# main_board.net
KiCad netlist of a schematic drawn in EAGLE
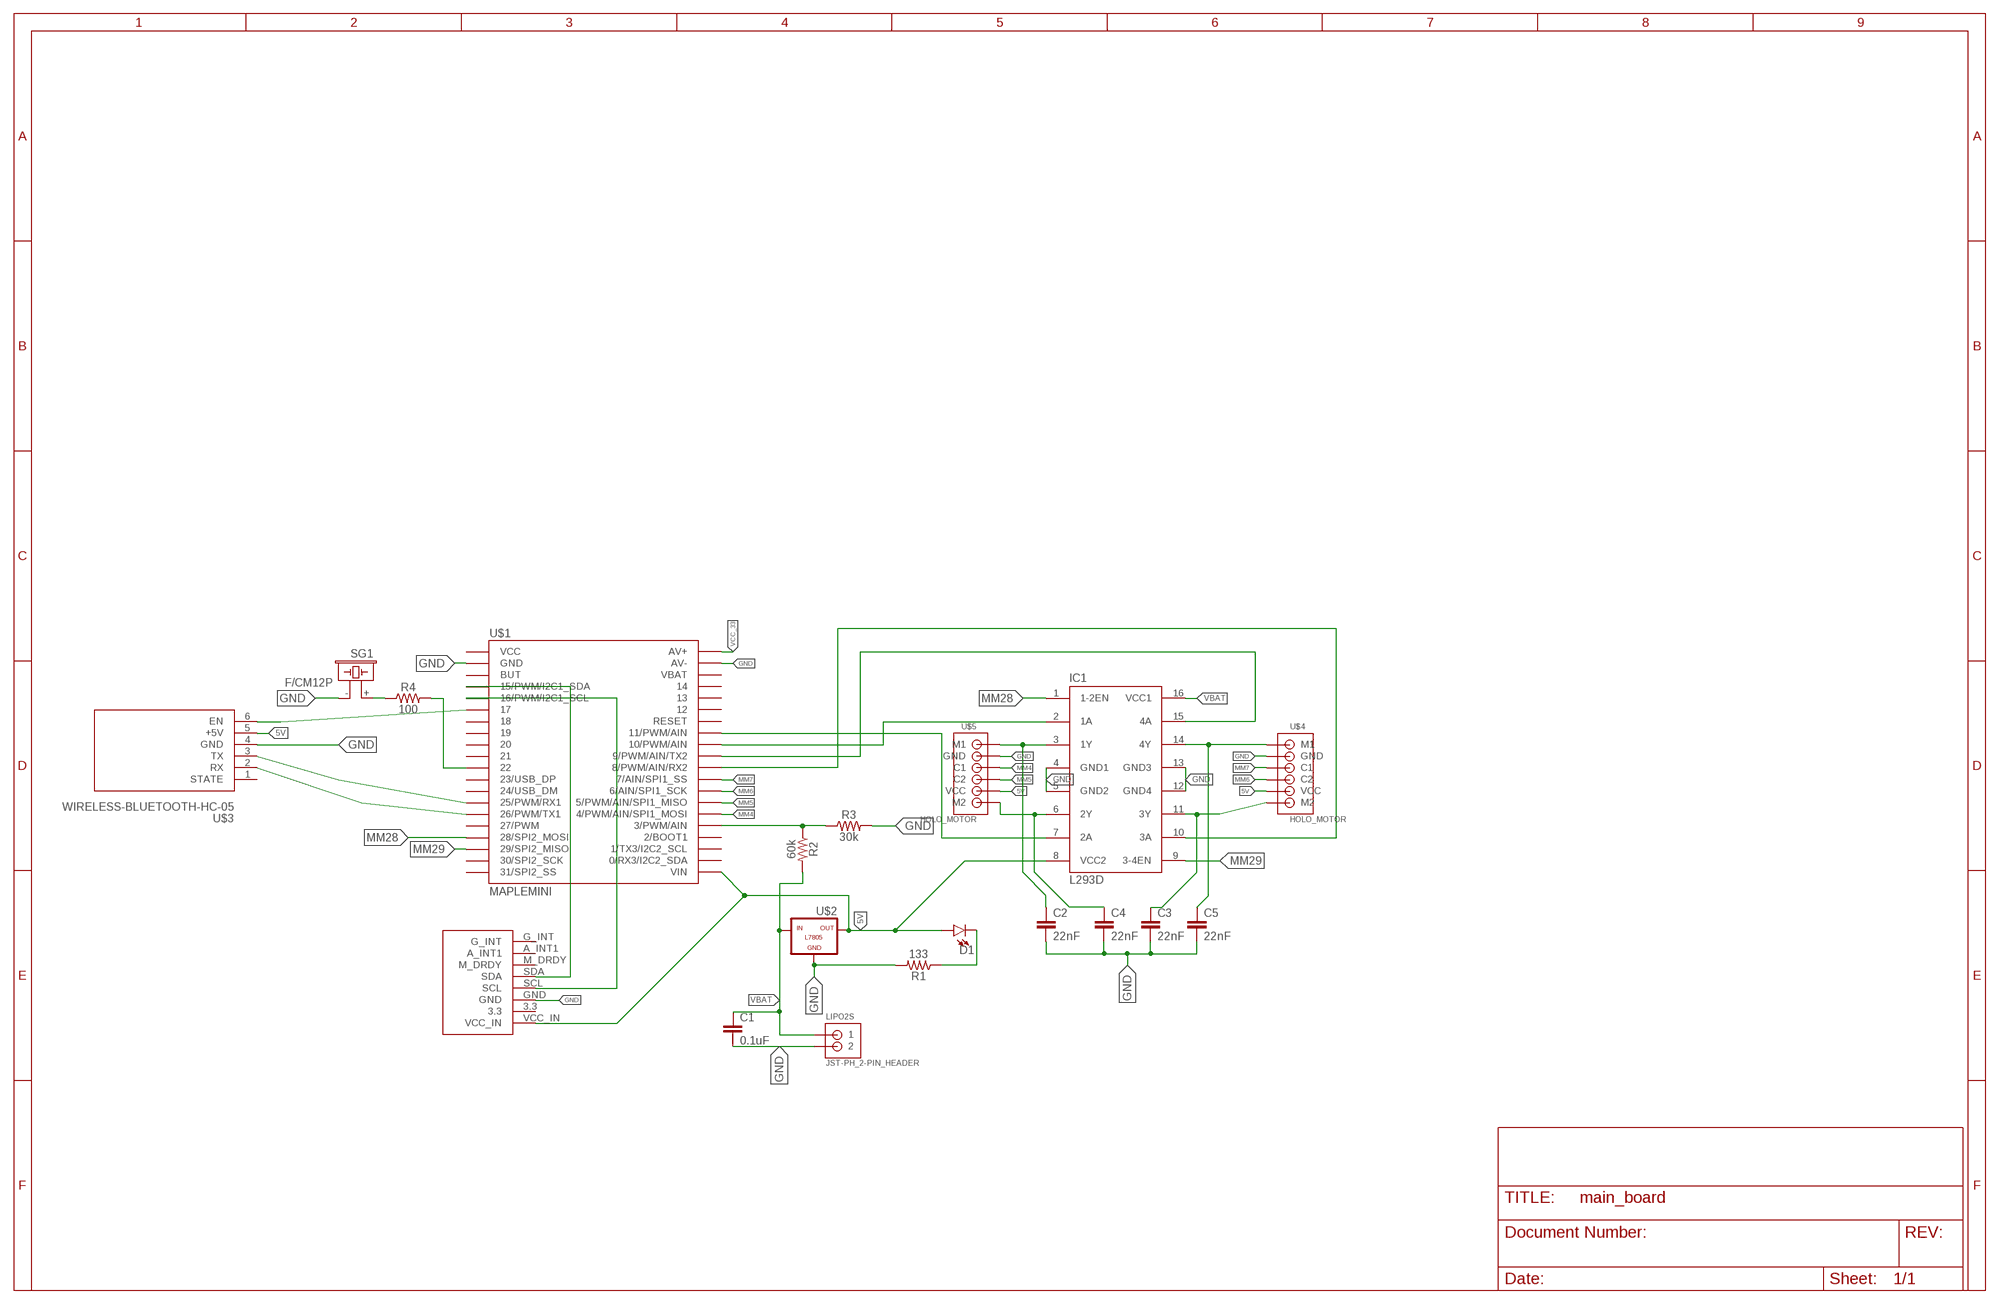
[diagram p0: schematic, sheet 1]

(export (version "E")
  (design (tool "Eeschema 10.0.6"))
  (components
    (comp (ref "C1")
      (value "0.1uF")
      (footprint "eagle-import:0603")
      (libsource (lib "eagle-import") (part "0.1UF-0603-25V-(+80/-20%)"))
    )
    (comp (ref "C2")
      (value "22nF")
      (footprint "eagle-import:0603")
      (libsource (lib "eagle-import") (part "22NF/22,000PF-0603-50V-10%"))
    )
    (comp (ref "C3")
      (value "22nF")
      (footprint "eagle-import:0603")
      (libsource (lib "eagle-import") (part "22NF/22,000PF-0603-50V-10%"))
    )
    (comp (ref "C4")
      (value "22nF")
      (footprint "eagle-import:0603")
      (libsource (lib "eagle-import") (part "22NF/22,000PF-0603-50V-10%"))
    )
    (comp (ref "C5")
      (value "22nF")
      (footprint "eagle-import:0603")
      (libsource (lib "eagle-import") (part "22NF/22,000PF-0603-50V-10%"))
    )
    (comp (ref "D1")
      (value "LED-FKIT-1206")
      (footprint "eagle-import:FKIT-LED-1206")
      (libsource (lib "eagle-import") (part "LED-FKIT-1206"))
    )
    (comp (ref "IC1")
      (value "L293D")
      (footprint "eagle-import:DIL16")
      (libsource (lib "eagle-import") (part "L293D"))
    )
    (comp (ref "LIPO2S")
      (value "JST-PH_2-PIN_HEADER")
      (footprint "eagle-import:JST_B2B-PH_HEADER")
      (libsource (lib "eagle-import") (part "JST-PH_2-PIN_HEADER"))
    )
    (comp (ref "R1")
      (value "133")
      (footprint "eagle-import:0603")
      (libsource (lib "eagle-import") (part "0.27OHM-0603-1/10W-1%"))
    )
    (comp (ref "R2")
      (value "60k")
      (footprint "eagle-import:0603")
      (libsource (lib "eagle-import") (part "0.27OHM-0603-1/10W-1%"))
    )
    (comp (ref "R3")
      (value "30k")
      (footprint "eagle-import:0603")
      (libsource (lib "eagle-import") (part "0.27OHM-0603-1/10W-1%"))
    )
    (comp (ref "R4")
      (value "100")
      (footprint "eagle-import:0603")
      (libsource (lib "eagle-import") (part "0.27OHM-0603-1/10W-1%"))
    )
    (comp (ref "SG1")
      (value "F/CM12P")
      (footprint "eagle-import:F_CM12P")
      (libsource (lib "eagle-import") (part "F/CM12P"))
    )
    (comp (ref "U$1")
      (value "MAPLEMINI")
      (footprint "eagle-import:20-DIP")
      (libsource (lib "eagle-import") (part "MAPLEMINI"))
    )
    (comp (ref "U$2")
      (value "-L7805")
      (footprint "eagle-import:L7805")
      (libsource (lib "eagle-import") (part "-L7805"))
    )
    (comp (ref "U$3")
      (value "WIRELESS-BLUETOOTH-HC-05")
      (footprint "eagle-import:WIRELESS-BLUETOOTH-HC-05")
      (libsource (lib "eagle-import") (part "WIRELESS-BLUETOOTH-HC-05"))
    )
    (comp (ref "U$4")
      (value "HOLO_MOTOR")
      (footprint "eagle-import:HOLO_MOTOR")
      (libsource (lib "eagle-import") (part "HOLO_MOTOR"))
    )
    (comp (ref "U$5")
      (value "HOLO_MOTOR")
      (footprint "eagle-import:HOLO_MOTOR")
      (libsource (lib "eagle-import") (part "HOLO_MOTOR"))
    )
    (comp (ref "U$6")
      (value "GY-85")
      (footprint "eagle-import:GY-85")
      (libsource (lib "eagle-import") (part "GY-85"))
    )
  )
  (nets
    (net (code "1") (name "5V") (class "Default")
      (node (ref "D1") (pin "A") (pinfunction "A_A") (pintype "passive"))
      (node (ref "IC1") (pin "8") (pinfunction "VCC2_8") (pintype "power_in"))
      (node (ref "U$1") (pin "21") (pinfunction "VIN_21") (pintype "bidirectional"))
      (node (ref "U$2") (pin "OUT") (pinfunction "OUT_OUT") (pintype "passive"))
      (node (ref "U$3") (pin "5") (pinfunction "+5V_5") (pintype "power_in"))
      (node (ref "U$4") (pin "5") (pinfunction "VCC_5") (pintype "bidirectional"))
      (node (ref "U$5") (pin "5") (pinfunction "VCC_5") (pintype "bidirectional"))
      (node (ref "U$6") (pin "VCC_IN") (pinfunction "VCC_IN_VCC_IN") (pintype "bidirectional"))
    )
    (net (code "2") (name "GND") (class "Default")
      (node (ref "C1") (pin "2") (pinfunction "2_2") (pintype "passive"))
      (node (ref "C2") (pin "2") (pinfunction "2_2") (pintype "passive"))
      (node (ref "C3") (pin "2") (pinfunction "2_2") (pintype "passive"))
      (node (ref "C4") (pin "2") (pinfunction "2_2") (pintype "passive"))
      (node (ref "C5") (pin "2") (pinfunction "2_2") (pintype "passive"))
      (node (ref "IC1") (pin "12") (pinfunction "GND4_12") (pintype "power_in"))
      (node (ref "IC1") (pin "13") (pinfunction "GND3_13") (pintype "power_in"))
      (node (ref "IC1") (pin "4") (pinfunction "GND1_4") (pintype "power_in"))
      (node (ref "IC1") (pin "5") (pinfunction "GND2_5") (pintype "power_in"))
      (node (ref "LIPO2S") (pin "P2") (pinfunction "2_P2") (pintype "bidirectional"))
      (node (ref "R1") (pin "2") (pinfunction "2_2") (pintype "passive"))
      (node (ref "R3") (pin "2") (pinfunction "2_2") (pintype "passive"))
      (node (ref "SG1") (pin "-") (pinfunction "2_-") (pintype "passive"))
      (node (ref "U$1") (pin "2") (pinfunction "GND_2") (pintype "bidirectional"))
      (node (ref "U$1") (pin "39") (pinfunction "AV-_39") (pintype "bidirectional"))
      (node (ref "U$2") (pin "GND") (pinfunction "GND_GND") (pintype "input"))
      (node (ref "U$3") (pin "4") (pinfunction "GND_4") (pintype "power_in"))
      (node (ref "U$4") (pin "2") (pinfunction "GND_2") (pintype "bidirectional"))
      (node (ref "U$5") (pin "2") (pinfunction "GND_2") (pintype "bidirectional"))
      (node (ref "U$6") (pin "GND") (pinfunction "GND_GND") (pintype "bidirectional"))
    )
    (net (code "3") (name "MM4") (class "Default")
      (node (ref "U$1") (pin "26") (pinfunction "4/PWM/AIN/SPI1_MOSI_26") (pintype "bidirectional"))
      (node (ref "U$5") (pin "3") (pinfunction "C1_3") (pintype "bidirectional"))
    )
    (net (code "4") (name "MM5") (class "Default")
      (node (ref "U$1") (pin "27") (pinfunction "5/PWM/AIN/SPI1_MISO_27") (pintype "bidirectional"))
      (node (ref "U$5") (pin "4") (pinfunction "C2_4") (pintype "bidirectional"))
    )
    (net (code "5") (name "MM6") (class "Default")
      (node (ref "U$1") (pin "28") (pinfunction "6/AIN/SPI1_SCK_28") (pintype "bidirectional"))
      (node (ref "U$4") (pin "4") (pinfunction "C2_4") (pintype "bidirectional"))
    )
    (net (code "6") (name "MM7") (class "Default")
      (node (ref "U$1") (pin "29") (pinfunction "7/AIN/SPI1_SS_29") (pintype "bidirectional"))
      (node (ref "U$4") (pin "3") (pinfunction "C1_3") (pintype "bidirectional"))
    )
    (net (code "7") (name "MM28") (class "Default")
      (node (ref "IC1") (pin "1") (pinfunction "1-2EN_1") (pintype "input"))
      (node (ref "U$1") (pin "17") (pinfunction "28/SPI2_MOSI_17") (pintype "bidirectional"))
    )
    (net (code "8") (name "MM29") (class "Default")
      (node (ref "IC1") (pin "9") (pinfunction "3-4EN_9") (pintype "input"))
      (node (ref "U$1") (pin "18") (pinfunction "29/SPI2_MISO_18") (pintype "bidirectional"))
    )
    (net (code "9") (name "Net-(D1-PadC)") (class "Default")
      (node (ref "D1") (pin "C") (pinfunction "C_C") (pintype "passive"))
      (node (ref "R1") (pin "1") (pinfunction "1_1") (pintype "passive"))
    )
    (net (code "10") (name "Net-(IC1-1A)") (class "Default")
      (node (ref "IC1") (pin "2") (pinfunction "1A_2") (pintype "input"))
      (node (ref "U$1") (pin "32") (pinfunction "10/PWM/AIN_32") (pintype "bidirectional"))
    )
    (net (code "11") (name "Net-(IC1-1Y)") (class "Default")
      (node (ref "C2") (pin "1") (pinfunction "1_1") (pintype "passive"))
      (node (ref "IC1") (pin "3") (pinfunction "1Y_3") (pintype "output"))
      (node (ref "U$5") (pin "1") (pinfunction "M1_1") (pintype "bidirectional"))
    )
    (net (code "12") (name "Net-(IC1-2A)") (class "Default")
      (node (ref "IC1") (pin "7") (pinfunction "2A_7") (pintype "input"))
      (node (ref "U$1") (pin "33") (pinfunction "11/PWM/AIN_33") (pintype "bidirectional"))
    )
    (net (code "13") (name "Net-(IC1-2Y)") (class "Default")
      (node (ref "C4") (pin "1") (pinfunction "1_1") (pintype "passive"))
      (node (ref "IC1") (pin "6") (pinfunction "2Y_6") (pintype "output"))
      (node (ref "U$5") (pin "6") (pinfunction "M2_6") (pintype "bidirectional"))
    )
    (net (code "14") (name "Net-(IC1-3A)") (class "Default")
      (node (ref "IC1") (pin "10") (pinfunction "3A_10") (pintype "input"))
      (node (ref "U$1") (pin "30") (pinfunction "8/PWM/AIN/RX2_30") (pintype "bidirectional"))
    )
    (net (code "15") (name "Net-(IC1-3Y)") (class "Default")
      (node (ref "C3") (pin "1") (pinfunction "1_1") (pintype "passive"))
      (node (ref "IC1") (pin "11") (pinfunction "3Y_11") (pintype "output"))
      (node (ref "U$4") (pin "6") (pinfunction "M2_6") (pintype "bidirectional"))
    )
    (net (code "16") (name "Net-(IC1-4A)") (class "Default")
      (node (ref "IC1") (pin "15") (pinfunction "4A_15") (pintype "input"))
      (node (ref "U$1") (pin "31") (pinfunction "9/PWM/AIN/TX2_31") (pintype "bidirectional"))
    )
    (net (code "17") (name "Net-(IC1-4Y)") (class "Default")
      (node (ref "C5") (pin "1") (pinfunction "1_1") (pintype "passive"))
      (node (ref "IC1") (pin "14") (pinfunction "4Y_14") (pintype "output"))
      (node (ref "U$4") (pin "1") (pinfunction "M1_1") (pintype "bidirectional"))
    )
    (net (code "18") (name "Net-(SG1-1)") (class "Default")
      (node (ref "R4") (pin "1") (pinfunction "1_1") (pintype "passive"))
      (node (ref "SG1") (pin "+") (pinfunction "1_+") (pintype "passive"))
    )
    (net (code "19") (name "Net-(U$1-3{slash}PWM{slash}AIN)") (class "Default")
      (node (ref "R2") (pin "1") (pinfunction "1_1") (pintype "passive"))
      (node (ref "R3") (pin "1") (pinfunction "1_1") (pintype "passive"))
      (node (ref "U$1") (pin "25") (pinfunction "3/PWM/AIN_25") (pintype "bidirectional"))
    )
    (net (code "20") (name "Net-(U$1-15{slash}PWM{slash}I2C1_SDA)") (class "Default")
      (node (ref "U$1") (pin "4") (pinfunction "15/PWM/I2C1_SDA_4") (pintype "bidirectional"))
      (node (ref "U$6") (pin "SDA") (pinfunction "SDA_SDA") (pintype "bidirectional"))
    )
    (net (code "21") (name "Net-(U$1-16{slash}PWM{slash}I2C1_SCL)") (class "Default")
      (node (ref "U$1") (pin "5") (pinfunction "16/PWM/I2C1_SCL_5") (pintype "bidirectional"))
      (node (ref "U$6") (pin "SCL") (pinfunction "SCL_SCL") (pintype "bidirectional"))
    )
    (net (code "22") (name "Net-(U$1-17)") (class "Default")
      (node (ref "U$1") (pin "6") (pinfunction "17_6") (pintype "bidirectional"))
      (node (ref "U$3") (pin "6") (pinfunction "EN_6") (pintype "bidirectional"))
    )
    (net (code "23") (name "Net-(U$1-22)") (class "Default")
      (node (ref "R4") (pin "2") (pinfunction "2_2") (pintype "passive"))
      (node (ref "U$1") (pin "11") (pinfunction "22_11") (pintype "bidirectional"))
    )
    (net (code "24") (name "Net-(U$1-25{slash}PWM{slash}RX1)") (class "Default")
      (node (ref "U$1") (pin "14") (pinfunction "25/PWM/RX1_14") (pintype "bidirectional"))
      (node (ref "U$3") (pin "3") (pinfunction "TX_3") (pintype "bidirectional"))
    )
    (net (code "25") (name "Net-(U$1-26{slash}PWM{slash}TX1)") (class "Default")
      (node (ref "U$1") (pin "15") (pinfunction "26/PWM/TX1_15") (pintype "bidirectional"))
      (node (ref "U$3") (pin "2") (pinfunction "RX_2") (pintype "bidirectional"))
    )
    (net (code "26") (name "VBAT") (class "Default")
      (node (ref "C1") (pin "1") (pinfunction "1_1") (pintype "passive"))
      (node (ref "IC1") (pin "16") (pinfunction "VCC1_16") (pintype "power_in"))
      (node (ref "LIPO2S") (pin "P1") (pinfunction "1_P1") (pintype "bidirectional"))
      (node (ref "R2") (pin "2") (pinfunction "2_2") (pintype "passive"))
      (node (ref "U$2") (pin "IN") (pinfunction "IN_IN") (pintype "input"))
    )
    (net (code "27") (name "VCC_33") (class "Default")
      (node (ref "U$1") (pin "40") (pinfunction "AV+_40") (pintype "bidirectional"))
    )
    (net (code "28") (name "unconnected-(U$1-0{slash}RX3{slash}I2C2_SDA-Pad22)") (class "Default")
      (node (ref "U$1") (pin "22") (pinfunction "0/RX3/I2C2_SDA_22") (pintype "bidirectional"))
    )
    (net (code "29") (name "unconnected-(U$1-1{slash}TX3{slash}I2C2_SCL-Pad23)") (class "Default")
      (node (ref "U$1") (pin "23") (pinfunction "1/TX3/I2C2_SCL_23") (pintype "bidirectional"))
    )
    (net (code "30") (name "unconnected-(U$1-2{slash}BOOT1-Pad24)") (class "Default")
      (node (ref "U$1") (pin "24") (pinfunction "2/BOOT1_24") (pintype "bidirectional"))
    )
    (net (code "31") (name "unconnected-(U$1-12-Pad35)") (class "Default")
      (node (ref "U$1") (pin "35") (pinfunction "12_35") (pintype "bidirectional"))
    )
    (net (code "32") (name "unconnected-(U$1-13-Pad36)") (class "Default")
      (node (ref "U$1") (pin "36") (pinfunction "13_36") (pintype "bidirectional"))
    )
    (net (code "33") (name "unconnected-(U$1-14-Pad37)") (class "Default")
      (node (ref "U$1") (pin "37") (pinfunction "14_37") (pintype "bidirectional"))
    )
    (net (code "34") (name "unconnected-(U$1-18-Pad7)") (class "Default")
      (node (ref "U$1") (pin "7") (pinfunction "18_7") (pintype "bidirectional"))
    )
    (net (code "35") (name "unconnected-(U$1-19-Pad8)") (class "Default")
      (node (ref "U$1") (pin "8") (pinfunction "19_8") (pintype "bidirectional"))
    )
    (net (code "36") (name "unconnected-(U$1-20-Pad9)") (class "Default")
      (node (ref "U$1") (pin "9") (pinfunction "20_9") (pintype "bidirectional"))
    )
    (net (code "37") (name "unconnected-(U$1-21-Pad10)") (class "Default")
      (node (ref "U$1") (pin "10") (pinfunction "21_10") (pintype "bidirectional"))
    )
    (net (code "38") (name "unconnected-(U$1-23{slash}USB_DP-Pad12)") (class "Default")
      (node (ref "U$1") (pin "12") (pinfunction "23/USB_DP_12") (pintype "bidirectional"))
    )
    (net (code "39") (name "unconnected-(U$1-24{slash}USB_DM-Pad13)") (class "Default")
      (node (ref "U$1") (pin "13") (pinfunction "24/USB_DM_13") (pintype "bidirectional"))
    )
    (net (code "40") (name "unconnected-(U$1-27{slash}PWM-Pad16)") (class "Default")
      (node (ref "U$1") (pin "16") (pinfunction "27/PWM_16") (pintype "bidirectional"))
    )
    (net (code "41") (name "unconnected-(U$1-30{slash}SPI2_SCK-Pad19)") (class "Default")
      (node (ref "U$1") (pin "19") (pinfunction "30/SPI2_SCK_19") (pintype "bidirectional"))
    )
    (net (code "42") (name "unconnected-(U$1-31{slash}SPI2_SS-Pad20)") (class "Default")
      (node (ref "U$1") (pin "20") (pinfunction "31/SPI2_SS_20") (pintype "bidirectional"))
    )
    (net (code "43") (name "unconnected-(U$1-BUT-Pad3)") (class "Default")
      (node (ref "U$1") (pin "3") (pinfunction "BUT_3") (pintype "bidirectional"))
    )
    (net (code "44") (name "unconnected-(U$1-RESET-Pad34)") (class "Default")
      (node (ref "U$1") (pin "34") (pinfunction "RESET_34") (pintype "bidirectional"))
    )
    (net (code "45") (name "unconnected-(U$1-VBAT-Pad38)") (class "Default")
      (node (ref "U$1") (pin "38") (pinfunction "VBAT_38") (pintype "bidirectional"))
    )
    (net (code "46") (name "unconnected-(U$1-VCC-Pad1)") (class "Default")
      (node (ref "U$1") (pin "1") (pinfunction "VCC_1") (pintype "bidirectional"))
    )
    (net (code "47") (name "unconnected-(U$3-STATE-Pad1)") (class "Default")
      (node (ref "U$3") (pin "1") (pinfunction "STATE_1") (pintype "bidirectional"))
    )
    (net (code "48") (name "unconnected-(U$6-Pad3.3)") (class "Default")
      (node (ref "U$6") (pin "3.3") (pinfunction "3.3_3.3") (pintype "bidirectional"))
    )
    (net (code "49") (name "unconnected-(U$6-PadA_INT1)") (class "Default")
      (node (ref "U$6") (pin "A_INT1") (pinfunction "A_INT1_A_INT1") (pintype "bidirectional"))
    )
    (net (code "50") (name "unconnected-(U$6-PadG_INT)") (class "Default")
      (node (ref "U$6") (pin "G_INT") (pinfunction "G_INT_G_INT") (pintype "bidirectional"))
    )
    (net (code "51") (name "unconnected-(U$6-PadM_DRDY)") (class "Default")
      (node (ref "U$6") (pin "M_DRDY") (pinfunction "M_DRDY_M_DRDY") (pintype "bidirectional"))
    )
  )
)
